# morse.net
KiCad netlist of a schematic drawn in EAGLE
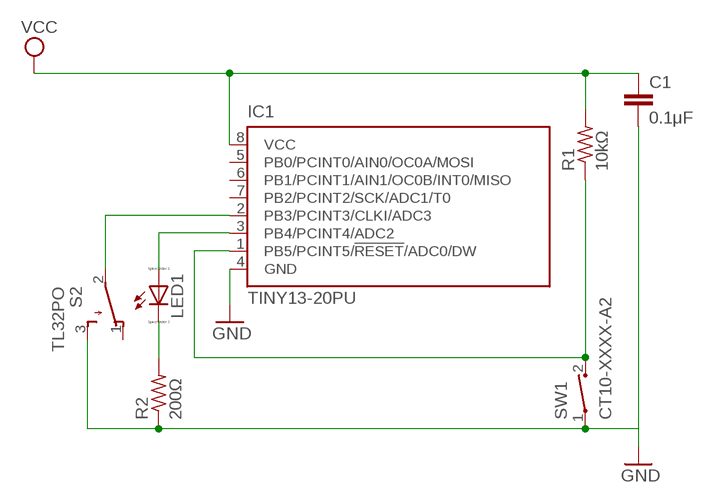
[diagram p0: schematic, sheet 1]

(export (version "E")
  (design (tool "Eeschema 10.0.6"))
  (components
    (comp (ref "C1")
      (value "0.1μF")
      (footprint "eagle-import:C2.5-3")
      (libsource (lib "eagle-import") (part "C2,5-3"))
    )
    (comp (ref "IC1")
      (value "TINY13-20PU")
      (footprint "eagle-import:DIL08")
      (fields (field (name "MPN") "ATTINY13-20PU"))
      (libsource (lib "eagle-import") (part "TINY13PU-20"))
    )
    (comp (ref "LED1")
      (value "LED_ELD260")
      (footprint "eagle-import:LED_LD260")
      (libsource (lib "eagle-import") (part "LED_ELD260"))
    )
    (comp (ref "R1")
      (value "10kΩ")
      (footprint "eagle-import:0204_7")
      (libsource (lib "eagle-import") (part "R-US_0204/7"))
    )
    (comp (ref "R2")
      (value "200Ω")
      (footprint "eagle-import:0204_7")
      (libsource (lib "eagle-import") (part "R-US_0204/7"))
    )
    (comp (ref "S2")
      (value "TL32PO")
      (footprint "eagle-import:TL3XPO")
      (libsource (lib "eagle-import") (part "TL32PO"))
    )
    (comp (ref "SW1")
      (value "CT10-XXXX-A2")
      (footprint "eagle-import:CT10-XXXX-A2")
      (libsource (lib "eagle-import") (part "CT10-XXXX-A2"))
    )
  )
  (nets
    (net (code "1") (name "GND") (class "Default")
      (node (ref "C1") (pin "2") (pinfunction "2_2") (pintype "passive"))
      (node (ref "IC1") (pin "4") (pinfunction "GND_4") (pintype "power_in"))
      (node (ref "R2") (pin "1") (pinfunction "1_1") (pintype "passive"))
      (node (ref "S2") (pin "3") (pinfunction "S_3") (pintype "passive"))
      (node (ref "SW1") (pin "1") (pinfunction "1_1") (pintype "passive"))
    )
    (net (code "2") (name "Net-(IC1-PB3{slash}PCINT3{slash}CLKI{slash}ADC3)") (class "Default")
      (node (ref "IC1") (pin "2") (pinfunction "PB3/PCINT3/CLKI/ADC3_2") (pintype "bidirectional"))
      (node (ref "S2") (pin "2") (pinfunction "P_2") (pintype "passive"))
    )
    (net (code "3") (name "Net-(IC1-PB4{slash}PCINT4{slash}ADC2)") (class "Default")
      (node (ref "IC1") (pin "3") (pinfunction "PB4/PCINT4/ADC2_3") (pintype "bidirectional"))
      (node (ref "LED1") (pin "A") (pinfunction "A_A") (pintype "passive"))
    )
    (net (code "4") (name "Net-(IC1-PB5{slash}PCINT5{slash}~{RESET}{slash}ADC0{slash}DW)") (class "Default")
      (node (ref "IC1") (pin "1") (pinfunction "PB5/PCINT5/~{RESET}/ADC0/DW_1") (pintype "bidirectional"))
      (node (ref "R1") (pin "1") (pinfunction "1_1") (pintype "passive"))
      (node (ref "SW1") (pin "2") (pinfunction "2_2") (pintype "passive"))
    )
    (net (code "5") (name "Net-(LED1-C)") (class "Default")
      (node (ref "LED1") (pin "K") (pinfunction "C_K") (pintype "passive"))
      (node (ref "R2") (pin "2") (pinfunction "2_2") (pintype "passive"))
    )
    (net (code "6") (name "VCC") (class "Default")
      (node (ref "C1") (pin "1") (pinfunction "1_1") (pintype "passive"))
      (node (ref "IC1") (pin "8") (pinfunction "VCC_8") (pintype "power_in"))
      (node (ref "R1") (pin "2") (pinfunction "2_2") (pintype "passive"))
    )
    (net (code "7") (name "unconnected-(IC1-PB0{slash}PCINT0{slash}AIN0{slash}OC0A{slash}MOSI-Pad5)") (class "Default")
      (node (ref "IC1") (pin "5") (pinfunction "PB0/PCINT0/AIN0/OC0A/MOSI_5") (pintype "bidirectional"))
    )
    (net (code "8") (name "unconnected-(IC1-PB1{slash}PCINT1{slash}AIN1{slash}OC0B{slash}INT0{slash}MISO-Pad6)") (class "Default")
      (node (ref "IC1") (pin "6") (pinfunction "PB1/PCINT1/AIN1/OC0B/INT0/MISO_6") (pintype "bidirectional"))
    )
    (net (code "9") (name "unconnected-(IC1-PB2{slash}PCINT2{slash}SCK{slash}ADC1{slash}T0-Pad7)") (class "Default")
      (node (ref "IC1") (pin "7") (pinfunction "PB2/PCINT2/SCK/ADC1/T0_7") (pintype "bidirectional"))
    )
    (net (code "10") (name "unconnected-(S2-O-Pad1)") (class "Default")
      (node (ref "S2") (pin "1") (pinfunction "O_1") (pintype "passive"))
    )
  )
)
